# shield.net
KiCad netlist of a schematic drawn in EAGLE
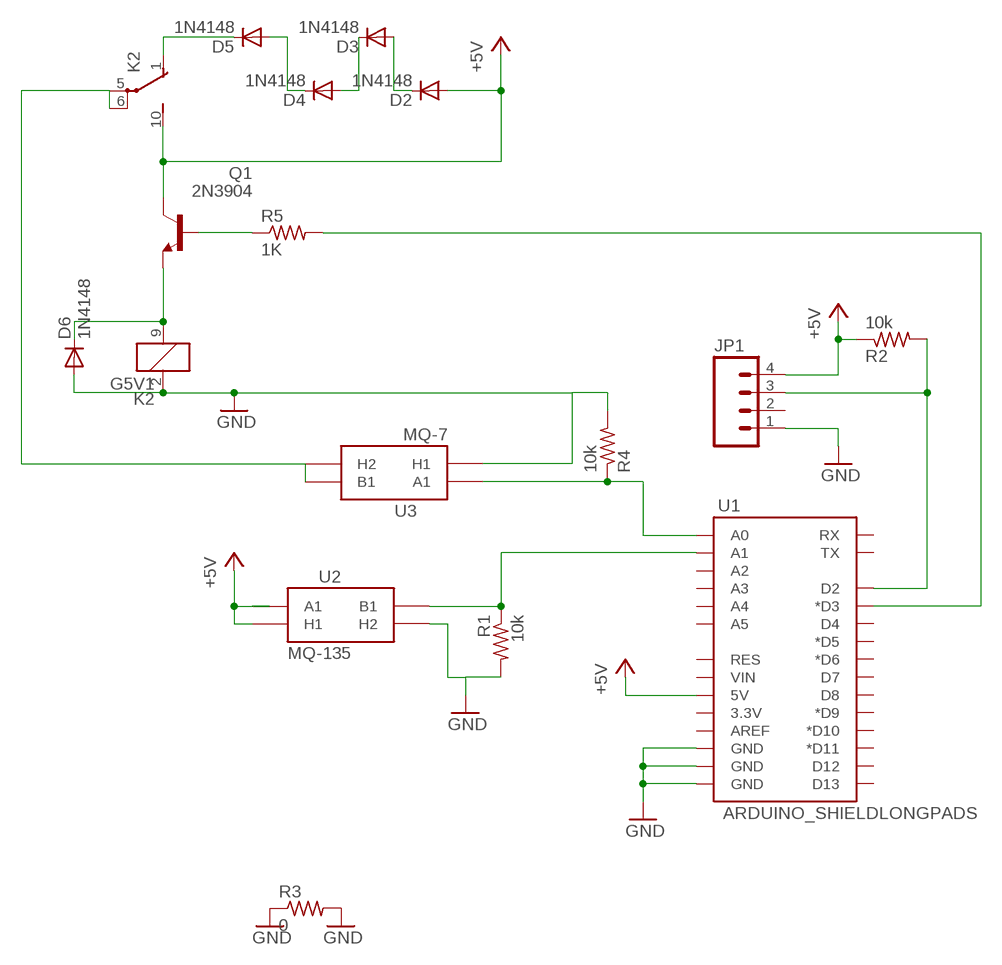
[diagram p0: schematic, sheet 1]

(export (version "E")
  (design (tool "Eeschema 10.0.6"))
  (components
    (comp (ref "D2")
      (value "1N4148")
      (footprint "eagle-import:DO35-7")
      (libsource (lib "eagle-import") (part "1N4148DO35-7"))
    )
    (comp (ref "D3")
      (value "1N4148")
      (footprint "eagle-import:DO35-7")
      (libsource (lib "eagle-import") (part "1N4148DO35-7"))
    )
    (comp (ref "D4")
      (value "1N4148")
      (footprint "eagle-import:DO35-7")
      (libsource (lib "eagle-import") (part "1N4148DO35-7"))
    )
    (comp (ref "D5")
      (value "1N4148")
      (footprint "eagle-import:DO35-7")
      (libsource (lib "eagle-import") (part "1N4148DO35-7"))
    )
    (comp (ref "D6")
      (value "1N4148")
      (footprint "eagle-import:DO35-7")
      (libsource (lib "eagle-import") (part "1N4148DO35-7"))
    )
    (comp (ref "JP1")
      (value "M04LONGPADS")
      (footprint "eagle-import:1X04_LONGPADS")
      (libsource (lib "eagle-import") (part "M04LONGPADS"))
    )
    (comp (ref "K2")
      (value "G5V1")
      (footprint "eagle-import:G5V1")
      (libsource (lib "eagle-import") (part "G5V1"))
    )
    (comp (ref "Q1")
      (value "2N3904")
      (footprint "eagle-import:TO92")
      (libsource (lib "eagle-import") (part "2N3904"))
    )
    (comp (ref "R1")
      (value "10k")
      (footprint "eagle-import:0204_7")
      (libsource (lib "eagle-import") (part "R-US_0204/7"))
    )
    (comp (ref "R2")
      (value "10k")
      (footprint "eagle-import:0204_7")
      (libsource (lib "eagle-import") (part "R-US_0204/7"))
    )
    (comp (ref "R3")
      (value "0")
      (footprint "eagle-import:0204_7")
      (libsource (lib "eagle-import") (part "resistor_R-US_0204/7"))
    )
    (comp (ref "R4")
      (value "10k")
      (footprint "eagle-import:0204_7")
      (libsource (lib "eagle-import") (part "R-US_0204/7"))
    )
    (comp (ref "R5")
      (value "1K")
      (footprint "eagle-import:0204_7")
      (libsource (lib "eagle-import") (part "resistor_R-US_0204/7"))
    )
    (comp (ref "U1")
      (value "ARDUINO_SHIELDLONGPADS")
      (footprint "eagle-import:DUEMILANOVE_SHIELD_LONGPADS")
      (libsource (lib "eagle-import") (part "ARDUINO_SHIELDLONGPADS"))
    )
    (comp (ref "U2")
      (value "MQ-135")
      (footprint "eagle-import:MQ-3")
      (libsource (lib "eagle-import") (part "SparkFun-Sensors_GAS_SENSOR"))
    )
    (comp (ref "U3")
      (value "MQ-7")
      (footprint "eagle-import:MQ-3")
      (libsource (lib "eagle-import") (part "GAS_SENSOR"))
    )
  )
  (nets
    (net (code "1") (name "+5V") (class "Default")
      (node (ref "D2") (pin "A") (pinfunction "A_A") (pintype "passive"))
      (node (ref "JP1") (pin "4") (pinfunction "4_4") (pintype "passive"))
      (node (ref "K2") (pin "10") (pinfunction "S_10") (pintype "passive"))
      (node (ref "Q1") (pin "1") (pinfunction "C_1") (pintype "passive"))
      (node (ref "R2") (pin "1") (pinfunction "1_1") (pintype "passive"))
      (node (ref "U1") (pin "5V") (pinfunction "5V_5V") (pintype "bidirectional"))
      (node (ref "U2") (pin "A1") (pinfunction "A1_A1") (pintype "bidirectional"))
      (node (ref "U2") (pin "HA") (pinfunction "H1_HA") (pintype "bidirectional"))
    )
    (net (code "2") (name "GND") (class "Default")
      (node (ref "D6") (pin "A") (pinfunction "A_A") (pintype "passive"))
      (node (ref "JP1") (pin "1") (pinfunction "1_1") (pintype "passive"))
      (node (ref "K2") (pin "2") (pinfunction "1_2") (pintype "passive"))
      (node (ref "R1") (pin "2") (pinfunction "2_2") (pintype "passive"))
      (node (ref "R3") (pin "1") (pinfunction "1_1") (pintype "passive"))
      (node (ref "R3") (pin "2") (pinfunction "2_2") (pintype "passive"))
      (node (ref "R4") (pin "2") (pinfunction "2_2") (pintype "passive"))
      (node (ref "U1") (pin "GND@0") (pinfunction "GND_GND@0") (pintype "bidirectional"))
      (node (ref "U1") (pin "GND@1") (pinfunction "GND_GND@1") (pintype "bidirectional"))
      (node (ref "U1") (pin "GND@2") (pinfunction "GND_GND@2") (pintype "bidirectional"))
      (node (ref "U2") (pin "HB") (pinfunction "H2_HB") (pintype "bidirectional"))
      (node (ref "U3") (pin "HA") (pinfunction "H1_HA") (pintype "bidirectional"))
    )
    (net (code "3") (name "Net-(D2-PadC)") (class "Default")
      (node (ref "D2") (pin "C") (pinfunction "C_C") (pintype "passive"))
      (node (ref "D3") (pin "A") (pinfunction "A_A") (pintype "passive"))
    )
    (net (code "4") (name "Net-(D3-PadC)") (class "Default")
      (node (ref "D3") (pin "C") (pinfunction "C_C") (pintype "passive"))
      (node (ref "D4") (pin "A") (pinfunction "A_A") (pintype "passive"))
    )
    (net (code "5") (name "Net-(D4-PadC)") (class "Default")
      (node (ref "D4") (pin "C") (pinfunction "C_C") (pintype "passive"))
      (node (ref "D5") (pin "A") (pinfunction "A_A") (pintype "passive"))
    )
    (net (code "6") (name "Net-(JP1-Pad3)") (class "Default")
      (node (ref "JP1") (pin "3") (pinfunction "3_3") (pintype "passive"))
      (node (ref "R2") (pin "2") (pinfunction "2_2") (pintype "passive"))
      (node (ref "U1") (pin "D2") (pinfunction "D2_D2") (pintype "bidirectional"))
    )
    (net (code "7") (name "Net-(K2A-2)") (class "Default")
      (node (ref "D6") (pin "C") (pinfunction "C_C") (pintype "passive"))
      (node (ref "K2") (pin "9") (pinfunction "2_9") (pintype "passive"))
      (node (ref "Q1") (pin "3") (pinfunction "E_3") (pintype "passive"))
    )
    (net (code "8") (name "Net-(K2B-O)") (class "Default")
      (node (ref "D5") (pin "C") (pinfunction "C_C") (pintype "passive"))
      (node (ref "K2") (pin "1") (pinfunction "O_1") (pintype "passive"))
    )
    (net (code "9") (name "Net-(Q1-B)") (class "Default")
      (node (ref "Q1") (pin "2") (pinfunction "B_2") (pintype "passive"))
      (node (ref "R5") (pin "1") (pinfunction "1_1") (pintype "passive"))
    )
    (net (code "10") (name "Net-(R1-Pad1)") (class "Default")
      (node (ref "R1") (pin "1") (pinfunction "1_1") (pintype "passive"))
      (node (ref "U1") (pin "A1") (pinfunction "A1_A1") (pintype "bidirectional"))
      (node (ref "U2") (pin "B1") (pinfunction "B1_B1") (pintype "bidirectional"))
    )
    (net (code "11") (name "Net-(R4-Pad1)") (class "Default")
      (node (ref "R4") (pin "1") (pinfunction "1_1") (pintype "passive"))
      (node (ref "U1") (pin "A0") (pinfunction "A0_A0") (pintype "bidirectional"))
      (node (ref "U3") (pin "A1") (pinfunction "A1_A1") (pintype "bidirectional"))
    )
    (net (code "12") (name "Net-(U1-*D3)") (class "Default")
      (node (ref "R5") (pin "2") (pinfunction "2_2") (pintype "passive"))
      (node (ref "U1") (pin "D3") (pinfunction "*D3_D3") (pintype "bidirectional"))
    )
    (net (code "13") (name "Net-(U3-H2)") (class "Default")
      (node (ref "K2") (pin "5") (pinfunction "P_5") (pintype "passive"))
      (node (ref "K2") (pin "6") (pinfunction "P_6") (pintype "passive"))
      (node (ref "U3") (pin "B1") (pinfunction "B1_B1") (pintype "bidirectional"))
      (node (ref "U3") (pin "HB") (pinfunction "H2_HB") (pintype "bidirectional"))
    )
    (net (code "14") (name "unconnected-(JP1-Pad2)") (class "Default")
      (node (ref "JP1") (pin "2") (pinfunction "2_2") (pintype "passive"))
    )
    (net (code "15") (name "unconnected-(U1-*D5-PadD5)") (class "Default")
      (node (ref "U1") (pin "D5") (pinfunction "*D5_D5") (pintype "bidirectional"))
    )
    (net (code "16") (name "unconnected-(U1-*D6-PadD6)") (class "Default")
      (node (ref "U1") (pin "D6") (pinfunction "*D6_D6") (pintype "bidirectional"))
    )
    (net (code "17") (name "unconnected-(U1-*D9-PadD9)") (class "Default")
      (node (ref "U1") (pin "D9") (pinfunction "*D9_D9") (pintype "bidirectional"))
    )
    (net (code "18") (name "unconnected-(U1-*D10-PadD10)") (class "Default")
      (node (ref "U1") (pin "D10") (pinfunction "*D10_D10") (pintype "bidirectional"))
    )
    (net (code "19") (name "unconnected-(U1-*D11-PadD11)") (class "Default")
      (node (ref "U1") (pin "D11") (pinfunction "*D11_D11") (pintype "bidirectional"))
    )
    (net (code "20") (name "unconnected-(U1-Pad3.3V)") (class "Default")
      (node (ref "U1") (pin "3.3V") (pinfunction "3.3V_3.3V") (pintype "bidirectional"))
    )
    (net (code "21") (name "unconnected-(U1-PadA2)") (class "Default")
      (node (ref "U1") (pin "A2") (pinfunction "A2_A2") (pintype "bidirectional"))
    )
    (net (code "22") (name "unconnected-(U1-PadA3)") (class "Default")
      (node (ref "U1") (pin "A3") (pinfunction "A3_A3") (pintype "bidirectional"))
    )
    (net (code "23") (name "unconnected-(U1-PadA4)") (class "Default")
      (node (ref "U1") (pin "A4") (pinfunction "A4_A4") (pintype "bidirectional"))
    )
    (net (code "24") (name "unconnected-(U1-PadA5)") (class "Default")
      (node (ref "U1") (pin "A5") (pinfunction "A5_A5") (pintype "bidirectional"))
    )
    (net (code "25") (name "unconnected-(U1-PadAREF)") (class "Default")
      (node (ref "U1") (pin "AREF") (pinfunction "AREF_AREF") (pintype "bidirectional"))
    )
    (net (code "26") (name "unconnected-(U1-PadD4)") (class "Default")
      (node (ref "U1") (pin "D4") (pinfunction "D4_D4") (pintype "bidirectional"))
    )
    (net (code "27") (name "unconnected-(U1-PadD7)") (class "Default")
      (node (ref "U1") (pin "D7") (pinfunction "D7_D7") (pintype "bidirectional"))
    )
    (net (code "28") (name "unconnected-(U1-PadD8)") (class "Default")
      (node (ref "U1") (pin "D8") (pinfunction "D8_D8") (pintype "bidirectional"))
    )
    (net (code "29") (name "unconnected-(U1-PadD12)") (class "Default")
      (node (ref "U1") (pin "D12") (pinfunction "D12_D12") (pintype "bidirectional"))
    )
    (net (code "30") (name "unconnected-(U1-PadD13)") (class "Default")
      (node (ref "U1") (pin "D13") (pinfunction "D13_D13") (pintype "bidirectional"))
    )
    (net (code "31") (name "unconnected-(U1-PadRES)") (class "Default")
      (node (ref "U1") (pin "RES") (pinfunction "RES_RES") (pintype "bidirectional"))
    )
    (net (code "32") (name "unconnected-(U1-PadRX)") (class "Default")
      (node (ref "U1") (pin "RX") (pinfunction "RX_RX") (pintype "bidirectional"))
    )
    (net (code "33") (name "unconnected-(U1-PadTX)") (class "Default")
      (node (ref "U1") (pin "TX") (pinfunction "TX_TX") (pintype "bidirectional"))
    )
    (net (code "34") (name "unconnected-(U1-PadVIN)") (class "Default")
      (node (ref "U1") (pin "VIN") (pinfunction "VIN_VIN") (pintype "bidirectional"))
    )
  )
)
